# UAARG_Autopilot.net
KiCad netlist of a schematic drawn in Altium Designer
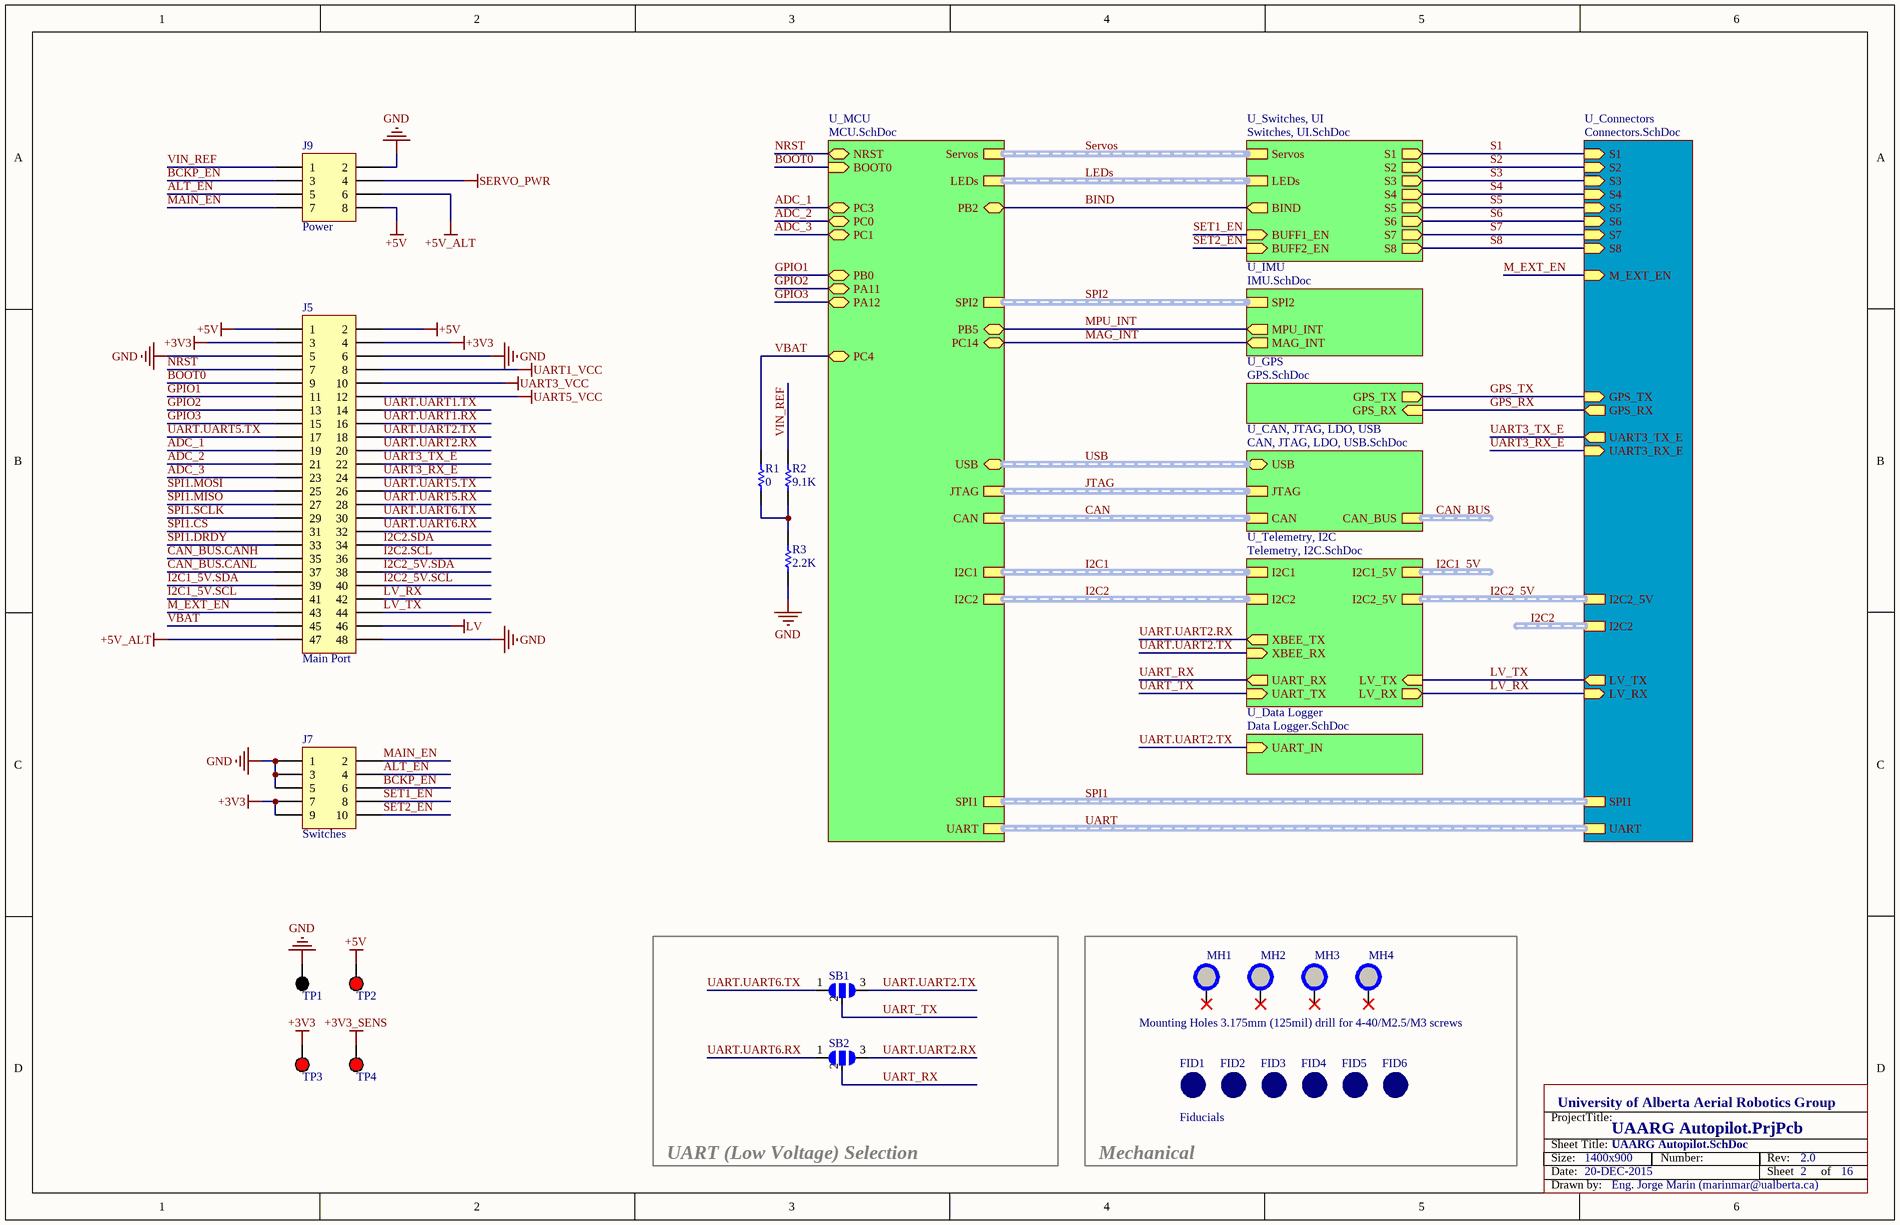
[diagram p0: UAARG Autopilot.SchDoc]

(export (version "E")
  (design (tool "Eeschema 10.0.6"))
  (components
    (comp (ref "FID1")
      (value "Ficudial")
      (footprint "FIDUCIAL_1")
      (description "Fiducial")
      (libsource (lib "UAARG Autopilot") (part "Ficudial"))
    )
    (comp (ref "FID2")
      (value "Ficudial")
      (footprint "FIDUCIAL_1")
      (description "Fiducial")
      (libsource (lib "UAARG Autopilot") (part "Ficudial"))
    )
    (comp (ref "FID3")
      (value "Ficudial")
      (footprint "FIDUCIAL_1")
      (description "Fiducial")
      (libsource (lib "UAARG Autopilot") (part "Ficudial"))
    )
    (comp (ref "FID4")
      (value "Ficudial")
      (footprint "FIDUCIAL_1")
      (description "Fiducial")
      (libsource (lib "UAARG Autopilot") (part "Ficudial"))
    )
    (comp (ref "FID5")
      (value "Ficudial")
      (footprint "FIDUCIAL_1")
      (description "Fiducial")
      (libsource (lib "UAARG Autopilot") (part "Ficudial"))
    )
    (comp (ref "FID6")
      (value "Ficudial")
      (footprint "FIDUCIAL_1")
      (description "Fiducial")
      (libsource (lib "UAARG Autopilot") (part "Ficudial"))
    )
    (comp (ref "J5")
      (value "Main Port")
      (footprint "HDR_2X24")
      (description "Header, 24-Pin, Dual row")
      (libsource (lib "Miscellaneous Connectors") (part "Header 24X2"))
    )
    (comp (ref "J7")
      (value "Switches")
      (footprint "HDR_2X05")
      (description "Header, 5-Pin, Dual row")
      (libsource (lib "Miscellaneous Connectors") (part "Header 5X2"))
    )
    (comp (ref "J9")
      (value "Power")
      (footprint "2X04")
      (description "Header, 4-Pin, Dual row")
      (libsource (lib "Miscellaneous Connectors") (part "Header 4X2"))
    )
    (comp (ref "MH1")
      (value "Mounting Hole")
      (footprint "MOUNTINGHOLE_6")
      (libsource (lib "UAARG Autopilot") (part "Mounting Hole"))
    )
    (comp (ref "MH2")
      (value "Mounting Hole")
      (footprint "MOUNTINGHOLE_6")
      (libsource (lib "UAARG Autopilot") (part "Mounting Hole"))
    )
    (comp (ref "MH3")
      (value "Mounting Hole")
      (footprint "MOUNTINGHOLE_6")
      (libsource (lib "UAARG Autopilot") (part "Mounting Hole"))
    )
    (comp (ref "MH4")
      (value "Mounting Hole")
      (footprint "MOUNTINGHOLE_6")
      (libsource (lib "UAARG Autopilot") (part "Mounting Hole"))
    )
    (comp (ref "R1")
      (value "0")
      (footprint "RES_0402[1005M]")
      (description "Resistor")
      (fields
        (field (name "MANUFACTURER PART NUMBER") "RC0402JR-070RL")
        (field (name "MANUFACTURER") "Yageo")
      )
      (libsource (lib "UAARG Autopilot") (part "RES"))
    )
    (comp (ref "R2")
      (value "9.1K")
      (footprint "RES_0603[1608M]")
      (description "Resistor")
      (fields
        (field (name "MANUFACTURER PART NUMBER") "RC0603FR-079K1L")
        (field (name "MANUFACTURER") "Yageo")
      )
      (libsource (lib "UAARG Autopilot") (part "RES"))
    )
    (comp (ref "R3")
      (value "2.2K")
      (footprint "RES_0603[1608M]")
      (description "Resistor")
      (fields
        (field (name "MANUFACTURER") "Yageo")
        (field (name "MANUFACTURER PART NUMBER") "RC0603FR-072K2L")
      )
      (libsource (lib "UAARG Autopilot") (part "RES"))
    )
    (comp (ref "SB1")
      (value "SMD Jumper 1")
      (footprint "SMD JUMPER 1")
      (description "SMD Jumper 3 positions. Open")
      (libsource (lib "UAARG Autopilot") (part "SMD Jumper 1"))
    )
    (comp (ref "SB2")
      (value "SMD Jumper 1")
      (footprint "SMD JUMPER 1")
      (description "SMD Jumper 3 positions. Open")
      (libsource (lib "UAARG Autopilot") (part "SMD Jumper 1"))
    )
    (comp (ref "TP1")
      (value "Test Point GND")
      (footprint "TP_TH_1_SILK")
      (description "Test Point Ground")
      (libsource (lib "UAARG Autopilot") (part "Test Point GND"))
    )
    (comp (ref "TP2")
      (value "Test Point VCC")
      (footprint "TP_TH_1_SILK")
      (description "Test Point Power")
      (libsource (lib "UAARG Autopilot") (part "Test Point VCC"))
    )
    (comp (ref "TP3")
      (value "Test Point VCC")
      (footprint "TP_TH_1_SILK")
      (description "Test Point Power")
      (libsource (lib "UAARG Autopilot") (part "Test Point VCC"))
    )
    (comp (ref "TP4")
      (value "Test Point VCC")
      (footprint "TP_TH_1_SILK")
      (description "Test Point Power")
      (libsource (lib "UAARG Autopilot") (part "Test Point VCC"))
    )
  )
  (nets
    (net (code "14") (name "+3V3") (class "Default")
      (node (ref "J5") (pin "3") (pinfunction "3_3") (pintype "passive"))
      (node (ref "J5") (pin "4") (pinfunction "4_4") (pintype "passive"))
      (node (ref "J7") (pin "7") (pinfunction "7_7") (pintype "passive"))
      (node (ref "J7") (pin "9") (pinfunction "9_9") (pintype "passive"))
      (node (ref "TP3") (pin "1") (pinfunction "1_1") (pintype "passive"))
    )
    (net (code "15") (name "+3V3_SENS") (class "Default")
      (node (ref "TP4") (pin "1") (pinfunction "1_1") (pintype "passive"))
    )
    (net (code "16") (name "+5V") (class "Default")
      (node (ref "J5") (pin "1") (pinfunction "1_1") (pintype "passive"))
      (node (ref "J5") (pin "2") (pinfunction "2_2") (pintype "passive"))
      (node (ref "J9") (pin "8") (pinfunction "8_8") (pintype "passive"))
      (node (ref "TP2") (pin "1") (pinfunction "1_1") (pintype "passive"))
    )
    (net (code "17") (name "+5V_ALT") (class "Default")
      (node (ref "J5") (pin "47") (pinfunction "47_47") (pintype "passive"))
      (node (ref "J9") (pin "6") (pinfunction "6_6") (pintype "passive"))
    )
    (net (code "18") (name "/ADC_1") (class "Default")
      (node (ref "J5") (pin "19") (pinfunction "19_19") (pintype "passive"))
    )
    (net (code "19") (name "/ADC_2") (class "Default")
      (node (ref "J5") (pin "21") (pinfunction "21_21") (pintype "passive"))
    )
    (net (code "20") (name "/ADC_3") (class "Default")
      (node (ref "J5") (pin "23") (pinfunction "23_23") (pintype "passive"))
    )
    (net (code "21") (name "/ALT_EN") (class "Default")
      (node (ref "J7") (pin "4") (pinfunction "4_4") (pintype "passive"))
      (node (ref "J9") (pin "5") (pinfunction "5_5") (pintype "passive"))
    )
    (net (code "22") (name "/BCKP_EN") (class "Default")
      (node (ref "J7") (pin "6") (pinfunction "6_6") (pintype "passive"))
      (node (ref "J9") (pin "3") (pinfunction "3_3") (pintype "passive"))
    )
    (net (code "24") (name "/BOOT0") (class "Default")
      (node (ref "J5") (pin "9") (pinfunction "9_9") (pintype "passive"))
    )
    (net (code "25") (name "/CAN_BUS.CANH") (class "Default")
      (node (ref "J5") (pin "35") (pinfunction "35_35") (pintype "passive"))
    )
    (net (code "26") (name "/CAN_BUS.CANL") (class "Default")
      (node (ref "J5") (pin "37") (pinfunction "37_37") (pintype "passive"))
    )
    (net (code "27") (name "/GPIO1") (class "Default")
      (node (ref "J5") (pin "11") (pinfunction "11_11") (pintype "passive"))
    )
    (net (code "28") (name "/GPIO2") (class "Default")
      (node (ref "J5") (pin "13") (pinfunction "13_13") (pintype "passive"))
    )
    (net (code "29") (name "/GPIO3") (class "Default")
      (node (ref "J5") (pin "15") (pinfunction "15_15") (pintype "passive"))
    )
    (net (code "32") (name "/I2C1_5V.SCL") (class "Default")
      (node (ref "J5") (pin "41") (pinfunction "41_41") (pintype "passive"))
    )
    (net (code "33") (name "/I2C1_5V.SDA") (class "Default")
      (node (ref "J5") (pin "39") (pinfunction "39_39") (pintype "passive"))
    )
    (net (code "34") (name "/I2C2.SCL") (class "Default")
      (node (ref "J5") (pin "36") (pinfunction "36_36") (pintype "passive"))
    )
    (net (code "35") (name "/I2C2.SDA") (class "Default")
      (node (ref "J5") (pin "34") (pinfunction "34_34") (pintype "passive"))
    )
    (net (code "36") (name "/I2C2_5V.SCL") (class "Default")
      (node (ref "J5") (pin "40") (pinfunction "40_40") (pintype "passive"))
    )
    (net (code "37") (name "/I2C2_5V.SDA") (class "Default")
      (node (ref "J5") (pin "38") (pinfunction "38_38") (pintype "passive"))
    )
    (net (code "38") (name "/LV_RX") (class "Default")
      (node (ref "J5") (pin "42") (pinfunction "42_42") (pintype "passive"))
    )
    (net (code "39") (name "/LV_TX") (class "Default")
      (node (ref "J5") (pin "44") (pinfunction "44_44") (pintype "passive"))
    )
    (net (code "41") (name "/MAIN_EN") (class "Default")
      (node (ref "J7") (pin "2") (pinfunction "2_2") (pintype "passive"))
      (node (ref "J9") (pin "7") (pinfunction "7_7") (pintype "passive"))
    )
    (net (code "43") (name "/M_EXT_EN") (class "Default")
      (node (ref "J5") (pin "43") (pinfunction "43_43") (pintype "passive"))
    )
    (net (code "44") (name "/NRST") (class "Default")
      (node (ref "J5") (pin "7") (pinfunction "7_7") (pintype "passive"))
    )
    (net (code "53") (name "/SET1_EN") (class "Default")
      (node (ref "J7") (pin "8") (pinfunction "8_8") (pintype "passive"))
    )
    (net (code "54") (name "/SET2_EN") (class "Default")
      (node (ref "J7") (pin "10") (pinfunction "10_10") (pintype "passive"))
    )
    (net (code "55") (name "/SPI1.CS") (class "Default")
      (node (ref "J5") (pin "31") (pinfunction "31_31") (pintype "passive"))
    )
    (net (code "56") (name "/SPI1.DRDY") (class "Default")
      (node (ref "J5") (pin "33") (pinfunction "33_33") (pintype "passive"))
    )
    (net (code "57") (name "/SPI1.MISO") (class "Default")
      (node (ref "J5") (pin "27") (pinfunction "27_27") (pintype "passive"))
    )
    (net (code "58") (name "/SPI1.MOSI") (class "Default")
      (node (ref "J5") (pin "25") (pinfunction "25_25") (pintype "passive"))
    )
    (net (code "59") (name "/SPI1.SCLK") (class "Default")
      (node (ref "J5") (pin "29") (pinfunction "29_29") (pintype "passive"))
    )
    (net (code "60") (name "/UART.UART1.RX") (class "Default")
      (node (ref "J5") (pin "16") (pinfunction "16_16") (pintype "passive"))
    )
    (net (code "61") (name "/UART.UART1.TX") (class "Default")
      (node (ref "J5") (pin "14") (pinfunction "14_14") (pintype "passive"))
    )
    (net (code "62") (name "/UART.UART2.RX") (class "Default")
      (node (ref "J5") (pin "20") (pinfunction "20_20") (pintype "passive"))
      (node (ref "SB2") (pin "3") (pinfunction "3_3") (pintype "passive"))
    )
    (net (code "63") (name "/UART.UART2.TX") (class "Default")
      (node (ref "J5") (pin "18") (pinfunction "18_18") (pintype "passive"))
      (node (ref "SB1") (pin "3") (pinfunction "3_3") (pintype "passive"))
    )
    (net (code "64") (name "/UART.UART5.RX") (class "Default")
      (node (ref "J5") (pin "28") (pinfunction "28_28") (pintype "passive"))
    )
    (net (code "65") (name "/UART.UART5.TX") (class "Default")
      (node (ref "J5") (pin "17") (pinfunction "17_17") (pintype "passive"))
      (node (ref "J5") (pin "26") (pinfunction "26_26") (pintype "passive"))
    )
    (net (code "66") (name "/UART.UART6.RX") (class "Default")
      (node (ref "J5") (pin "32") (pinfunction "32_32") (pintype "passive"))
      (node (ref "SB2") (pin "1") (pinfunction "1_1") (pintype "passive"))
    )
    (net (code "67") (name "/UART.UART6.TX") (class "Default")
      (node (ref "J5") (pin "30") (pinfunction "30_30") (pintype "passive"))
      (node (ref "SB1") (pin "1") (pinfunction "1_1") (pintype "passive"))
    )
    (net (code "68") (name "/UART3_RX_E") (class "Default")
      (node (ref "J5") (pin "24") (pinfunction "24_24") (pintype "passive"))
    )
    (net (code "69") (name "/UART3_TX_E") (class "Default")
      (node (ref "J5") (pin "22") (pinfunction "22_22") (pintype "passive"))
    )
    (net (code "70") (name "/UART_RX") (class "Default")
      (node (ref "SB2") (pin "2") (pinfunction "2_2") (pintype "passive"))
    )
    (net (code "71") (name "/UART_TX") (class "Default")
      (node (ref "SB1") (pin "2") (pinfunction "2_2") (pintype "passive"))
    )
    (net (code "72") (name "/VBAT") (class "Default")
      (node (ref "J5") (pin "45") (pinfunction "45_45") (pintype "passive"))
      (node (ref "R1") (pin "2") (pinfunction "2_2") (pintype "passive"))
    )
    (net (code "73") (name "/VIN_REF") (class "Default")
      (node (ref "J9") (pin "1") (pinfunction "1_1") (pintype "passive"))
      (node (ref "R2") (pin "2") (pinfunction "2_2") (pintype "passive"))
    )
    (net (code "87") (name "GND") (class "Default")
      (node (ref "J5") (pin "48") (pinfunction "48_48") (pintype "passive"))
      (node (ref "J5") (pin "5") (pinfunction "5_5") (pintype "passive"))
      (node (ref "J5") (pin "6") (pinfunction "6_6") (pintype "passive"))
      (node (ref "J7") (pin "1") (pinfunction "1_1") (pintype "passive"))
      (node (ref "J7") (pin "3") (pinfunction "3_3") (pintype "passive"))
      (node (ref "J7") (pin "5") (pinfunction "5_5") (pintype "passive"))
      (node (ref "J9") (pin "2") (pinfunction "2_2") (pintype "passive"))
      (node (ref "R3") (pin "1") (pinfunction "1_1") (pintype "passive"))
      (node (ref "TP1") (pin "1") (pinfunction "1_1") (pintype "passive"))
    )
    (net (code "88") (name "LV") (class "Default")
      (node (ref "J5") (pin "46") (pinfunction "46_46") (pintype "passive"))
    )
    (net (code "89") (name "Net-(R1-Pad1)") (class "Default")
      (node (ref "R1") (pin "1") (pinfunction "1_1") (pintype "passive"))
      (node (ref "R2") (pin "1") (pinfunction "1_1") (pintype "passive"))
      (node (ref "R3") (pin "2") (pinfunction "2_2") (pintype "passive"))
    )
    (net (code "90") (name "SERVO_PWR") (class "Default")
      (node (ref "J9") (pin "4") (pinfunction "4_4") (pintype "passive"))
    )
    (net (code "91") (name "UART1_VCC") (class "Default")
      (node (ref "J5") (pin "8") (pinfunction "8_8") (pintype "passive"))
    )
    (net (code "92") (name "UART3_VCC") (class "Default")
      (node (ref "J5") (pin "10") (pinfunction "10_10") (pintype "passive"))
    )
    (net (code "93") (name "UART5_VCC") (class "Default")
      (node (ref "J5") (pin "12") (pinfunction "12_12") (pintype "passive"))
    )
    (net (code "94") (name "unconnected-(MH1-Pad1)") (class "Default")
      (node (ref "MH1") (pin "1") (pinfunction "1_1") (pintype "passive+no_connect"))
    )
    (net (code "95") (name "unconnected-(MH2-Pad1)") (class "Default")
      (node (ref "MH2") (pin "1") (pinfunction "1_1") (pintype "passive+no_connect"))
    )
    (net (code "96") (name "unconnected-(MH3-Pad1)") (class "Default")
      (node (ref "MH3") (pin "1") (pinfunction "1_1") (pintype "passive+no_connect"))
    )
    (net (code "97") (name "unconnected-(MH4-Pad1)") (class "Default")
      (node (ref "MH4") (pin "1") (pinfunction "1_1") (pintype "passive+no_connect"))
    )
  )
)
